# TopLevel.net
KiCad netlist of a schematic drawn in Altium Designer
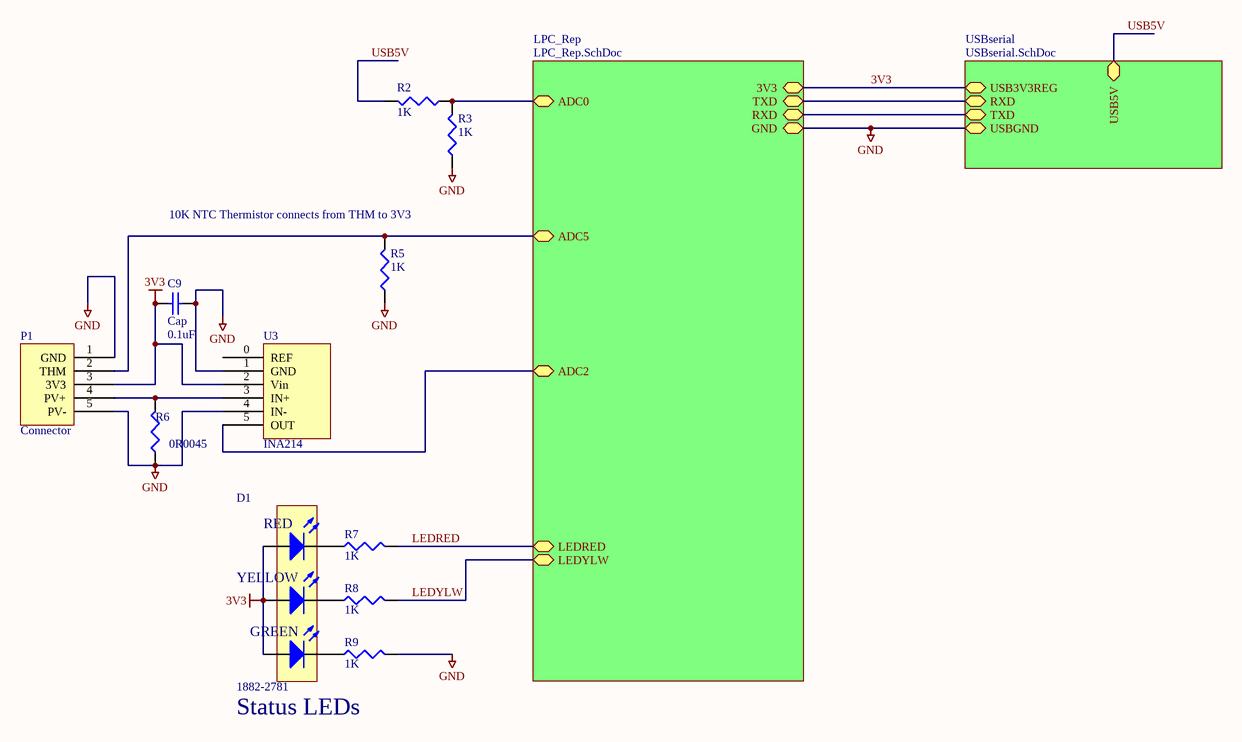
[diagram p0: TopLevel.SchDoc]

(export (version "E")
  (design (tool "Eeschema 10.0.6"))
  (components
    (comp (ref "C9")
      (value "Cap")
      (footprint "0603")
      (description "Capacitor")
      (fields (field (name "ALTIUM_VALUE") "0.1uF") (field (name "PUBLISHER") "Altium Limited"))
      (libsource (lib "Miscellaneous Devices") (part "Cap"))
    )
    (comp (ref "D1")
      (value "1882-2781")
      (footprint "LED_TRILEVEL")
      (description "Three level LED")
      (libsource (lib "RCLDQ") (part "LED-TRILEVEL"))
    )
    (comp (ref "P1") (value "Connector") (footprint "TermBlock5") (libsource (lib "SunRef") (part "CONN")))
    (comp (ref "R2")
      (value "1K")
      (footprint "0603")
      (description "Resistor")
      (libsource (lib "RCLDQ") (part "RES1"))
    )
    (comp (ref "R3")
      (value "1K")
      (footprint "0603")
      (description "Resistor")
      (libsource (lib "RCLDQ") (part "RES1"))
    )
    (comp (ref "R5")
      (value "1K")
      (footprint "0603")
      (description "Resistor")
      (libsource (lib "RCLDQ") (part "RES1"))
    )
    (comp (ref "R6")
      (value "0R0045")
      (footprint "1206")
      (description "Resistor")
      (libsource (lib "RCLDQ") (part "RES1"))
    )
    (comp (ref "R7")
      (value "1K")
      (footprint "0603")
      (description "Resistor")
      (libsource (lib "RCLDQ") (part "RES1"))
    )
    (comp (ref "R8")
      (value "1K")
      (footprint "0603")
      (description "Resistor")
      (libsource (lib "RCLDQ") (part "RES1"))
    )
    (comp (ref "R9")
      (value "1K")
      (footprint "0603")
      (description "Resistor")
      (libsource (lib "RCLDQ") (part "RES1"))
    )
    (comp (ref "U3") (value "INA214") (footprint "SOP6 - INA214") (libsource (lib "SunRef") (part "INA214")))
  )
  (nets
    (net (code "1") (name "/ADC0") (class "Default")
      (node (ref "R2") (pin "1") (pinfunction "1_1") (pintype "passive"))
      (node (ref "R3") (pin "2") (pinfunction "2_2") (pintype "passive"))
    )
    (net (code "2") (name "/ADC2") (class "Default")
      (node (ref "U3") (pin "5") (pinfunction "OUT_5") (pintype "passive"))
    )
    (net (code "3") (name "/ADC5") (class "Default")
      (node (ref "P1") (pin "2") (pinfunction "THM_2") (pintype "passive"))
      (node (ref "R5") (pin "2") (pinfunction "2_2") (pintype "passive"))
    )
    (net (code "4") (name "/LEDRED") (class "Default")
      (node (ref "R7") (pin "2") (pinfunction "2_2") (pintype "passive"))
    )
    (net (code "5") (name "/LEDYLW") (class "Default")
      (node (ref "R8") (pin "2") (pinfunction "2_2") (pintype "passive"))
    )
    (net (code "8") (name "/USB5V") (class "Default")
      (node (ref "R2") (pin "2") (pinfunction "2_2") (pintype "passive"))
    )
    (net (code "9") (name "3V3") (class "Default")
      (node (ref "C9") (pin "1") (pinfunction "1_1") (pintype "passive"))
      (node (ref "D1") (pin "4") (pinfunction "A_4") (pintype "passive"))
      (node (ref "D1") (pin "5") (pinfunction "A_5") (pintype "passive"))
      (node (ref "D1") (pin "6") (pinfunction "A_6") (pintype "passive"))
      (node (ref "P1") (pin "3") (pinfunction "3V3_3") (pintype "passive"))
      (node (ref "U3") (pin "2") (pinfunction "Vin_2") (pintype "passive"))
    )
    (net (code "10") (name "GND") (class "Default")
      (node (ref "C9") (pin "2") (pinfunction "2_2") (pintype "passive"))
      (node (ref "P1") (pin "1") (pinfunction "GND_1") (pintype "passive"))
      (node (ref "P1") (pin "5") (pinfunction "PV-_5") (pintype "passive"))
      (node (ref "R3") (pin "1") (pinfunction "1_1") (pintype "passive"))
      (node (ref "R5") (pin "1") (pinfunction "1_1") (pintype "passive"))
      (node (ref "R6") (pin "1") (pinfunction "1_1") (pintype "passive"))
      (node (ref "R9") (pin "2") (pinfunction "2_2") (pintype "passive"))
      (node (ref "U3") (pin "1") (pinfunction "GND_1") (pintype "passive"))
      (node (ref "U3") (pin "4") (pinfunction "IN-_4") (pintype "passive"))
    )
    (net (code "11") (name "Net-(D1-K-Pad1)") (class "Default")
      (node (ref "D1") (pin "1") (pinfunction "K_1") (pintype "passive"))
      (node (ref "R9") (pin "1") (pinfunction "1_1") (pintype "passive"))
    )
    (net (code "12") (name "Net-(D1-K-Pad2)") (class "Default")
      (node (ref "D1") (pin "2") (pinfunction "K_2") (pintype "passive"))
      (node (ref "R8") (pin "1") (pinfunction "1_1") (pintype "passive"))
    )
    (net (code "13") (name "Net-(D1-K-Pad3)") (class "Default")
      (node (ref "D1") (pin "3") (pinfunction "K_3") (pintype "passive"))
      (node (ref "R7") (pin "1") (pinfunction "1_1") (pintype "passive"))
    )
    (net (code "14") (name "Net-(P1-PV+)") (class "Default")
      (node (ref "P1") (pin "4") (pinfunction "PV+_4") (pintype "passive"))
      (node (ref "R6") (pin "2") (pinfunction "2_2") (pintype "passive"))
      (node (ref "U3") (pin "3") (pinfunction "IN+_3") (pintype "passive"))
    )
    (net (code "15") (name "unconnected-(U3-REF-Pad0)") (class "Default")
      (node (ref "U3") (pin "0") (pinfunction "REF_0") (pintype "passive"))
    )
  )
)
